# USB.net
KiCad netlist of a schematic drawn in Altium Designer
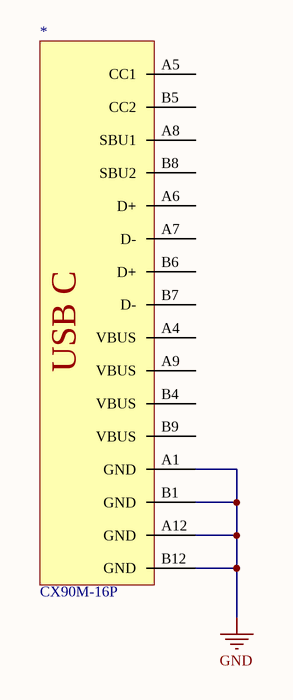
[diagram p0: USB.SchDoc]

(export (version "E")
  (design (tool "Eeschema 10.0.6"))
  (components
    (comp (ref "*")
      (value "CX90M-16P")
      (description "USB - C USB 3.0 (USB 3.1 Gen 1, Superspeed) Receptacle Connector 16 Position smt")
      (fields (field (name "MANUFACTURER") "Hirose"))
      (libsource (lib "USB_Sch") (part "CX90M-16P"))
    )
  )
  (nets
    (net (code "1") (name "GND") (class "Default")
      (node (ref "*") (pin "A1") (pinfunction "GND_A1") (pintype "passive"))
      (node (ref "*") (pin "A12") (pinfunction "GND_A12") (pintype "passive"))
      (node (ref "*") (pin "B1") (pinfunction "GND_B1") (pintype "passive"))
      (node (ref "*") (pin "B12") (pinfunction "GND_B12") (pintype "passive"))
    )
    (net (code "2") (name "unconnected-(*-CC1-PadA5)") (class "Default")
      (node (ref "*") (pin "A5") (pinfunction "CC1_A5") (pintype "passive"))
    )
    (net (code "3") (name "unconnected-(*-CC2-PadB5)") (class "Default")
      (node (ref "*") (pin "B5") (pinfunction "CC2_B5") (pintype "passive"))
    )
    (net (code "4") (name "unconnected-(*-D+-PadA6)") (class "Default")
      (node (ref "*") (pin "A6") (pinfunction "D+_A6") (pintype "passive"))
    )
    (net (code "5") (name "unconnected-(*-D+-PadB6)") (class "Default")
      (node (ref "*") (pin "B6") (pinfunction "D+_B6") (pintype "passive"))
    )
    (net (code "6") (name "unconnected-(*-D--PadA7)") (class "Default")
      (node (ref "*") (pin "A7") (pinfunction "D-_A7") (pintype "passive"))
    )
    (net (code "7") (name "unconnected-(*-D--PadB7)") (class "Default")
      (node (ref "*") (pin "B7") (pinfunction "D-_B7") (pintype "passive"))
    )
    (net (code "8") (name "unconnected-(*-SBU1-PadA8)") (class "Default")
      (node (ref "*") (pin "A8") (pinfunction "SBU1_A8") (pintype "passive"))
    )
    (net (code "9") (name "unconnected-(*-SBU2-PadB8)") (class "Default")
      (node (ref "*") (pin "B8") (pinfunction "SBU2_B8") (pintype "passive"))
    )
    (net (code "10") (name "unconnected-(*-VBUS-PadA4)") (class "Default")
      (node (ref "*") (pin "A4") (pinfunction "VBUS_A4") (pintype "passive"))
    )
    (net (code "11") (name "unconnected-(*-VBUS-PadA9)") (class "Default")
      (node (ref "*") (pin "A9") (pinfunction "VBUS_A9") (pintype "passive"))
    )
    (net (code "12") (name "unconnected-(*-VBUS-PadB4)") (class "Default")
      (node (ref "*") (pin "B4") (pinfunction "VBUS_B4") (pintype "passive"))
    )
    (net (code "13") (name "unconnected-(*-VBUS-PadB9)") (class "Default")
      (node (ref "*") (pin "B9") (pinfunction "VBUS_B9") (pintype "passive"))
    )
  )
)
